# Power_Supply.net
KiCad netlist of a schematic drawn in Altium Designer
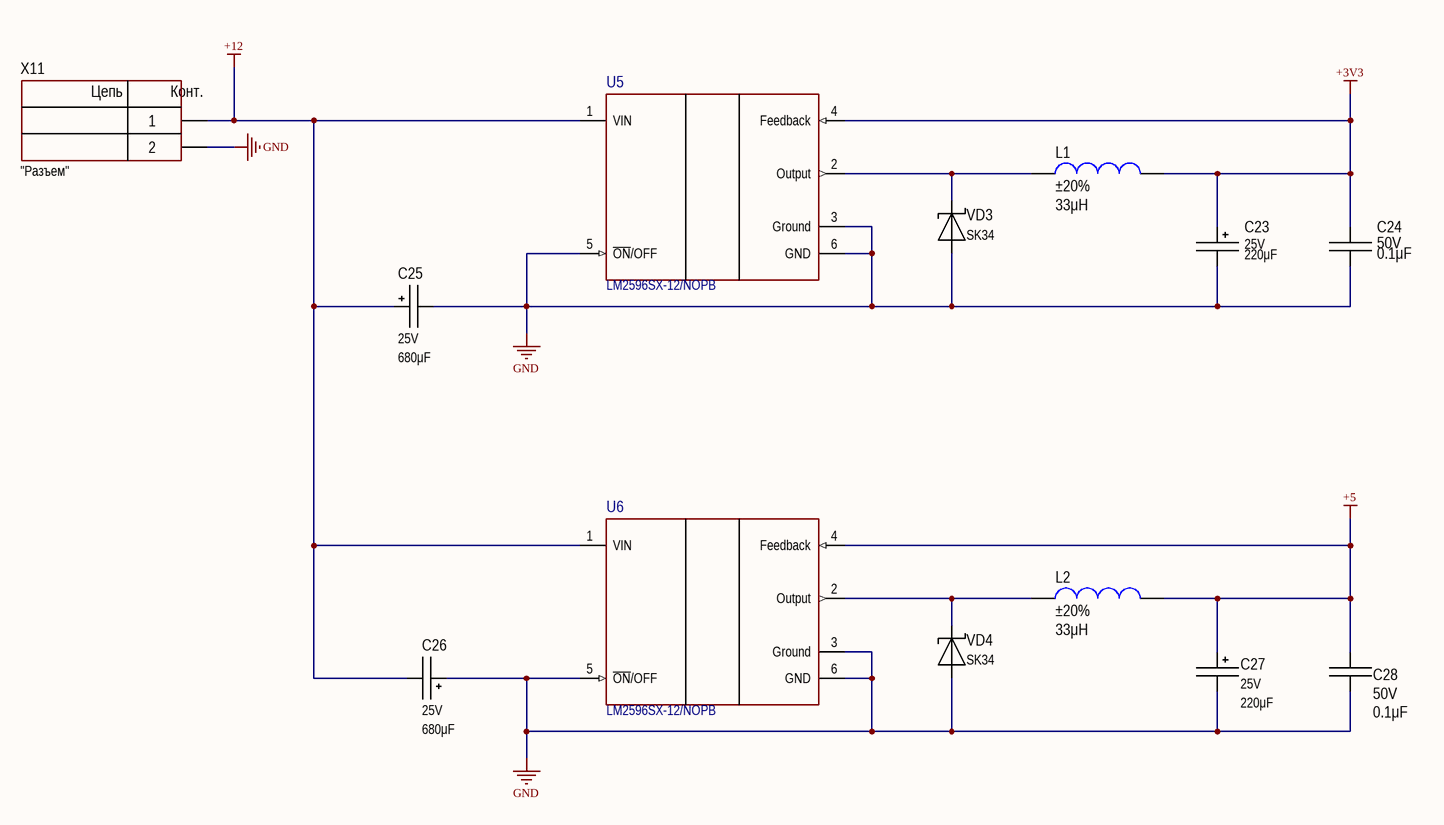
[diagram p0: Power_Supply.SchDoc]

(export (version "E")
  (design (tool "Eeschema 10.0.6"))
  (components
    (comp (ref "C23")
      (value "220μF")
      (footprint "standard-case:CAP: D10C5H16")
      (fields
        (field (name "MANUFACTURER") "Wurth")
        (field (name "PARTNUMBER") "860080475013")
        (field (name "VALUEMANUFACTURERPARTNUMBER") "Aluminium capacitor, 220μF, 25V, ±20%, 54mOhm, 14x10x5 mm, -55...+105°C")
        (field (name "VOLTAGE") "25V")
      )
      (libsource (lib "capacitor") (part "Aluminium"))
    )
    (comp (ref "C24")
      (value "0.1μF")
      (footprint "standard-case:CAP: 1206")
      (fields
        (field (name "MANUFACTURER") "Yageo")
        (field (name "PARTNUMBER") "CC1206KRX7R9BB104")
        (field (name "VALUEMANUFACTURERPARTNUMBER") "Ceramic capacitor, 0.1μF, X7R, ±10%, 50V, 1206, -55...+125°C")
        (field (name "VOLTAGE") "50V")
      )
      (libsource (lib "capacitor") (part "Ceramic_1206"))
    )
    (comp (ref "C25")
      (value "680μF")
      (footprint "standard-case:CAP: D10C5H16")
      (fields
        (field (name "MANUFACTURER") "Wurth")
        (field (name "PARTNUMBER") "860080475013")
        (field (name "VALUEMANUFACTURERPARTNUMBER") "Aluminium capacitor, 680μF, 25V, ±20%, 54mOhm, 14x10x5 mm, -55...+105°C")
        (field (name "VOLTAGE") "25V")
      )
      (libsource (lib "capacitor") (part "Aluminium"))
    )
    (comp (ref "C26")
      (value "680μF")
      (footprint "standard-case:CAP: D10C5H16")
      (fields
        (field (name "MANUFACTURER") "Wurth")
        (field (name "PARTNUMBER") "860080475013")
        (field (name "VALUEMANUFACTURERPARTNUMBER") "Aluminium capacitor, 680μF, 25V, ±20%, 54mOhm, 14x10x5 mm, -55...+105°C")
        (field (name "VOLTAGE") "25V")
      )
      (libsource (lib "capacitor") (part "Aluminium"))
    )
    (comp (ref "C27")
      (value "220μF")
      (footprint "standard-case:CAP: D10C5H16")
      (fields
        (field (name "MANUFACTURER") "Wurth")
        (field (name "PARTNUMBER") "860080475013")
        (field (name "VALUEMANUFACTURERPARTNUMBER") "Aluminium capacitor, 220μF, 25V, ±20%, 54mOhm, 14x10x5 mm, -55...+105°C")
        (field (name "VOLTAGE") "25V")
      )
      (libsource (lib "capacitor") (part "Aluminium"))
    )
    (comp (ref "C28")
      (value "0.1μF")
      (footprint "standard-case:CAP: 1206")
      (fields
        (field (name "MANUFACTURER") "Yageo")
        (field (name "PARTNUMBER") "CC1206KRX7R9BB104")
        (field (name "VALUEMANUFACTURERPARTNUMBER") "Ceramic capacitor, 0.1μF, X7R, ±10%, 50V, 1206, -55...+125°C")
        (field (name "VOLTAGE") "50V")
      )
      (libsource (lib "capacitor") (part "Ceramic_1206"))
    )
    (comp (ref "L1")
      (value "33μH")
      (footprint "SRR1208-101YL")
      (fields
        (field (name "MANUFACTURER") "Bourns")
        (field (name "PARTNUMBER") "SDR0403-4R7ML")
        (field (name "VALUEMANUFACTURERPARTNUMBER") "Fixed inductor, 33μH, ±20%, SDR0403, 1.7A, -40...+125°C")
        (field (name "TOLERANCE") "±20%")
      )
      (libsource (lib "SRR1208-101YL") (part "Inductor_SDR0403"))
    )
    (comp (ref "L2")
      (value "33μH")
      (footprint "SRR1208-101YL")
      (fields
        (field (name "MANUFACTURER") "Bourns")
        (field (name "PARTNUMBER") "SDR0403-4R7ML")
        (field (name "VALUEMANUFACTURERPARTNUMBER") "Fixed inductor, 33μH, ±20%, SDR0403, 1.7A, -40...+125°C")
        (field (name "TOLERANCE") "±20%")
      )
      (libsource (lib "SRR1208-101YL") (part "Inductor_SDR0403"))
    )
    (comp (ref "U5")
      (value "LM2596SX-12/NOPB")
      (footprint "FP-KTT0005B-MFG")
      (description "IC REG BUCK 12V 3A TO263-5")
      (fields
        (field (name "MANUFACTURER") "Texas Instruments")
        (field (name "OCTOPART") "https://octopart.com/lm2596sx-12%2Fnopb-texas+instruments-24812942")
      )
      (libsource (lib "LM2596SX-12NOPB") (part "CMP-04918-000013-1"))
    )
    (comp (ref "U6")
      (value "LM2596SX-12/NOPB")
      (footprint "FP-KTT0005B-MFG")
      (description "IC REG BUCK 12V 3A TO263-5")
      (fields
        (field (name "MANUFACTURER") "Texas Instruments")
        (field (name "OCTOPART") "https://octopart.com/lm2596sx-12%2Fnopb-texas+instruments-24812942")
      )
      (libsource (lib "LM2596SX-12NOPB") (part "CMP-04918-000013-1"))
    )
    (comp (ref "VD3")
      (value "~")
      (footprint "standard-case:DIODE: SMC")
      (fields
        (field (name "MANUFACTURER") "Diodes Incorporated")
        (field (name "VALUEMANUFACTURERPARTNUMBER") "Schottky diode, 80V, 500mA, 1V, 15pF, SOD-123, -55...+150°C")
        (field (name "VOLTAGE") "80V")
        (field (name "PARTNUMBER") "SK34")
      )
      (libsource (lib "diode") (part "Schottky_single"))
    )
    (comp (ref "VD4")
      (value "~")
      (footprint "standard-case:DIODE: SMC")
      (fields
        (field (name "MANUFACTURER") "Diodes Incorporated")
        (field (name "VALUEMANUFACTURERPARTNUMBER") "Schottky diode, 80V, 500mA, 1V, 15pF, SOD-123, -55...+150°C")
        (field (name "VOLTAGE") "80V")
        (field (name "PARTNUMBER") "SK34")
      )
      (libsource (lib "diode") (part "Schottky_single"))
    )
    (comp (ref "X11")
      (value "~")
      (footprint "custom-case:CON: DG350-3.5-02P")
      (fields
        (field (name "MANUFACTURER") "Degson")
        (field (name "VALUEMANUFACTURERPARTNUMBER") "Terminal connector, 2pin, 3.5mm, 300VAC, 10A")
        (field (name "PARTNUMBER") "DG350-3.5-02P-14")
        (field (name "COMMENTTEXT") "\"Разъем\"")
      )
      (libsource (lib "connector") (part "Connector_terminal_2pin"))
    )
  )
  (nets
    (net (code "1") (name "+3V3") (class "Default")
      (node (ref "C23") (pin "1") (pinfunction "1_1") (pintype "passive"))
      (node (ref "C24") (pin "2") (pinfunction "2_2") (pintype "passive"))
      (node (ref "L1") (pin "1") (pinfunction "1_1") (pintype "passive"))
      (node (ref "U5") (pin "4") (pinfunction "Feedback_4") (pintype "input"))
    )
    (net (code "2") (name "+5") (class "Default")
      (node (ref "C27") (pin "1") (pinfunction "1_1") (pintype "passive"))
      (node (ref "C28") (pin "2") (pinfunction "2_2") (pintype "passive"))
      (node (ref "L2") (pin "1") (pinfunction "1_1") (pintype "passive"))
      (node (ref "U6") (pin "4") (pinfunction "Feedback_4") (pintype "input"))
    )
    (net (code "3") (name "+12") (class "Default")
      (node (ref "C25") (pin "1") (pinfunction "1_1") (pintype "passive"))
      (node (ref "C26") (pin "2") (pinfunction "2_2") (pintype "passive"))
      (node (ref "U5") (pin "1") (pinfunction "VIN_1") (pintype "power_in"))
      (node (ref "U6") (pin "1") (pinfunction "VIN_1") (pintype "power_in"))
      (node (ref "X11") (pin "1") (pinfunction "1_1") (pintype "passive"))
    )
    (net (code "4") (name "GND") (class "Default")
      (node (ref "C23") (pin "2") (pinfunction "2_2") (pintype "passive"))
      (node (ref "C24") (pin "1") (pinfunction "1_1") (pintype "passive"))
      (node (ref "C25") (pin "2") (pinfunction "2_2") (pintype "passive"))
      (node (ref "C26") (pin "1") (pinfunction "1_1") (pintype "passive"))
      (node (ref "C27") (pin "2") (pinfunction "2_2") (pintype "passive"))
      (node (ref "C28") (pin "1") (pinfunction "1_1") (pintype "passive"))
      (node (ref "U5") (pin "3") (pinfunction "Ground_3") (pintype "power_in"))
      (node (ref "U5") (pin "5") (pinfunction "~{ON}/OFF_5") (pintype "input"))
      (node (ref "U5") (pin "6") (pinfunction "GND_6") (pintype "power_in"))
      (node (ref "U6") (pin "3") (pinfunction "Ground_3") (pintype "power_in"))
      (node (ref "U6") (pin "5") (pinfunction "~{ON}/OFF_5") (pintype "input"))
      (node (ref "U6") (pin "6") (pinfunction "GND_6") (pintype "power_in"))
      (node (ref "VD3") (pin "1") (pinfunction "1_1") (pintype "passive"))
      (node (ref "VD4") (pin "1") (pinfunction "1_1") (pintype "passive"))
      (node (ref "X11") (pin "2") (pinfunction "2_2") (pintype "passive"))
    )
    (net (code "5") (name "Net-(U5-Output)") (class "Default")
      (node (ref "L1") (pin "2") (pinfunction "2_2") (pintype "passive"))
      (node (ref "U5") (pin "2") (pinfunction "Output_2") (pintype "output"))
      (node (ref "VD3") (pin "2") (pinfunction "2_2") (pintype "passive"))
    )
    (net (code "6") (name "Net-(U6-Output)") (class "Default")
      (node (ref "L2") (pin "2") (pinfunction "2_2") (pintype "passive"))
      (node (ref "U6") (pin "2") (pinfunction "Output_2") (pintype "output"))
      (node (ref "VD4") (pin "2") (pinfunction "2_2") (pintype "passive"))
    )
  )
)
